# FPGA_C.net
KiCad netlist of a schematic drawn in Altium Designer
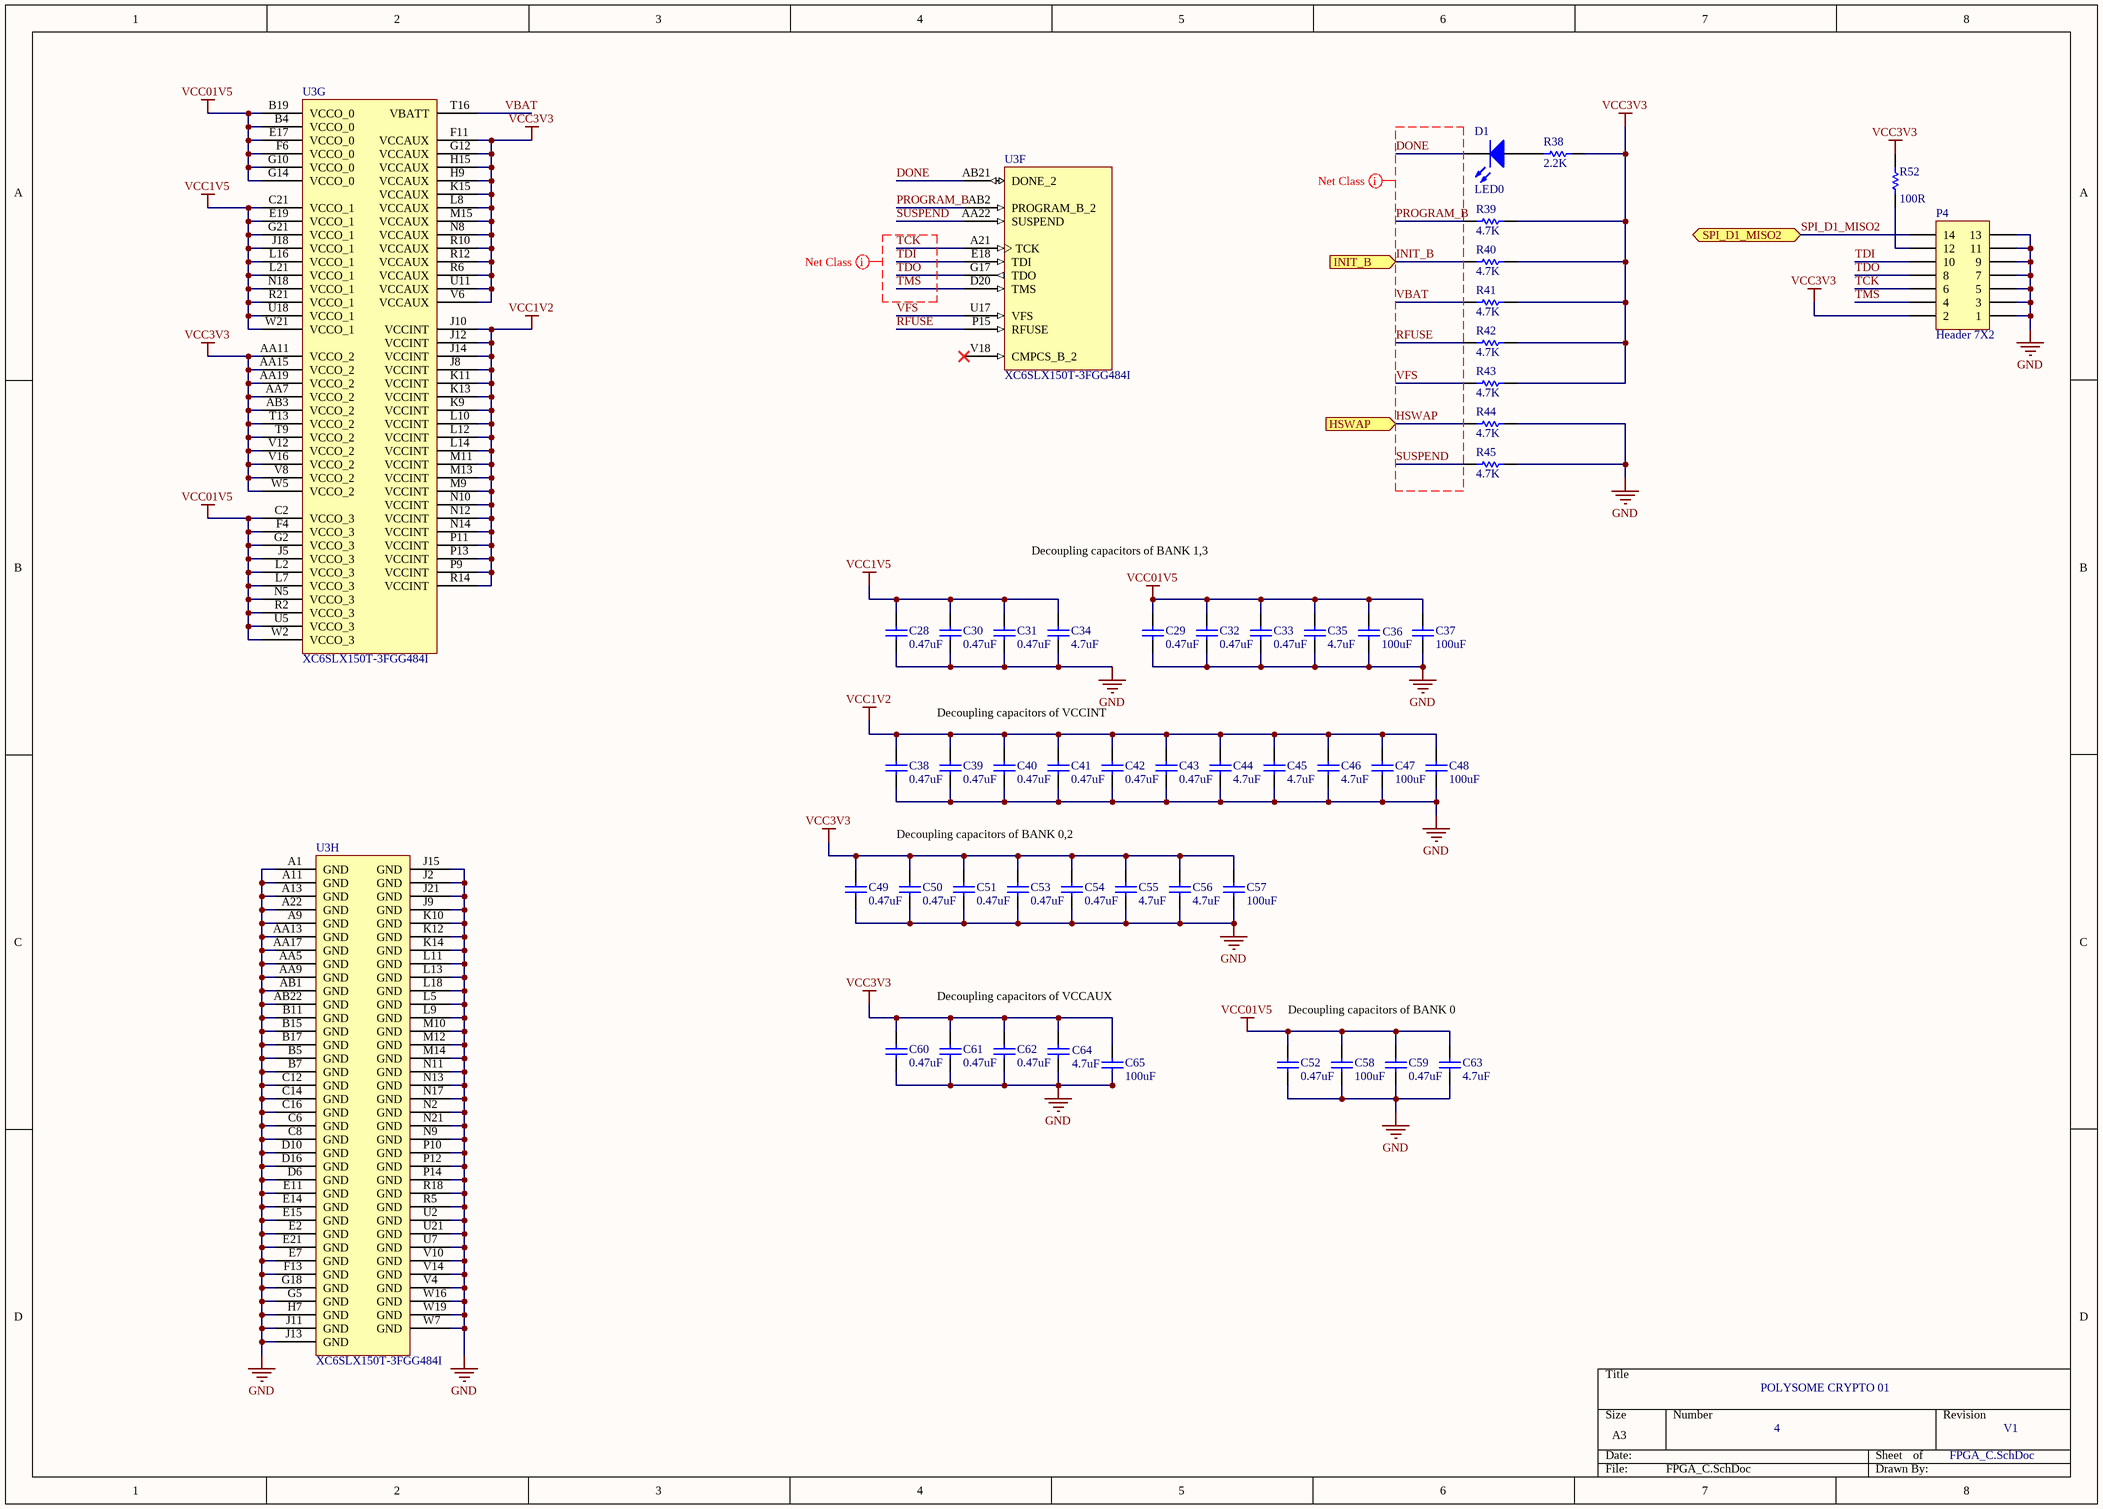
[diagram p0: FPGA_C.SchDoc]

(export (version "E")
  (design (tool "Eeschema 10.0.6"))
  (components
    (comp (ref "C28")
      (value "0.47uF")
      (footprint "0402")
      (description "Capacitor (Semiconductor SIM Model)")
      (fields (field (name "Comment") "Cap Semi") (field (name "PUBLISHER") "Altium Limited"))
      (libsource (lib "Miscellaneous Devices") (part "Cap Semi"))
    )
    (comp (ref "C29")
      (value "0.47uF")
      (footprint "0402")
      (description "Capacitor (Semiconductor SIM Model)")
      (fields (field (name "Comment") "Cap Semi") (field (name "PUBLISHER") "Altium Limited"))
      (libsource (lib "Miscellaneous Devices") (part "Cap Semi"))
    )
    (comp (ref "C30")
      (value "0.47uF")
      (footprint "0402")
      (description "Capacitor (Semiconductor SIM Model)")
      (fields (field (name "Comment") "Cap Semi") (field (name "PUBLISHER") "Altium Limited"))
      (libsource (lib "Miscellaneous Devices") (part "Cap Semi"))
    )
    (comp (ref "C31")
      (value "0.47uF")
      (footprint "0402")
      (description "Capacitor (Semiconductor SIM Model)")
      (fields (field (name "Comment") "Cap Semi") (field (name "PUBLISHER") "Altium Limited"))
      (libsource (lib "Miscellaneous Devices") (part "Cap Semi"))
    )
    (comp (ref "C32")
      (value "0.47uF")
      (footprint "0402")
      (description "Capacitor (Semiconductor SIM Model)")
      (fields (field (name "Comment") "Cap Semi") (field (name "PUBLISHER") "Altium Limited"))
      (libsource (lib "Miscellaneous Devices") (part "Cap Semi"))
    )
    (comp (ref "C33")
      (value "0.47uF")
      (footprint "0402")
      (description "Capacitor (Semiconductor SIM Model)")
      (fields (field (name "Comment") "Cap Semi") (field (name "PUBLISHER") "Altium Limited"))
      (libsource (lib "Miscellaneous Devices") (part "Cap Semi"))
    )
    (comp (ref "C34")
      (value "4.7uF")
      (footprint "1608[0603]")
      (description "Capacitor (Semiconductor SIM Model)")
      (fields (field (name "Comment") "Cap Semi") (field (name "PUBLISHER") "Altium Limited"))
      (libsource (lib "Miscellaneous Devices") (part "Cap Semi"))
    )
    (comp (ref "C35")
      (value "4.7uF")
      (footprint "1608[0603]")
      (description "Capacitor (Semiconductor SIM Model)")
      (fields (field (name "Comment") "Cap Semi") (field (name "PUBLISHER") "Altium Limited"))
      (libsource (lib "Miscellaneous Devices") (part "Cap Semi"))
    )
    (comp (ref "C36")
      (value "100uF")
      (footprint "0402")
      (description "Capacitor (Semiconductor SIM Model)")
      (fields (field (name "Comment") "Cap Semi") (field (name "PUBLISHER") "Altium Limited"))
      (libsource (lib "Miscellaneous Devices") (part "Cap Semi"))
    )
    (comp (ref "C37")
      (value "100uF")
      (footprint "0402")
      (description "Capacitor (Semiconductor SIM Model)")
      (fields (field (name "Comment") "Cap Semi") (field (name "PUBLISHER") "Altium Limited"))
      (libsource (lib "Miscellaneous Devices") (part "Cap Semi"))
    )
    (comp (ref "C38")
      (value "0.47uF")
      (footprint "0402")
      (description "Capacitor (Semiconductor SIM Model)")
      (fields (field (name "Comment") "Cap Semi") (field (name "PUBLISHER") "Altium Limited"))
      (libsource (lib "Miscellaneous Devices") (part "Cap Semi"))
    )
    (comp (ref "C39")
      (value "0.47uF")
      (footprint "0402")
      (description "Capacitor (Semiconductor SIM Model)")
      (fields (field (name "Comment") "Cap Semi") (field (name "PUBLISHER") "Altium Limited"))
      (libsource (lib "Miscellaneous Devices") (part "Cap Semi"))
    )
    (comp (ref "C40")
      (value "0.47uF")
      (footprint "0402")
      (description "Capacitor (Semiconductor SIM Model)")
      (fields (field (name "Comment") "Cap Semi") (field (name "PUBLISHER") "Altium Limited"))
      (libsource (lib "Miscellaneous Devices") (part "Cap Semi"))
    )
    (comp (ref "C41")
      (value "0.47uF")
      (footprint "0402")
      (description "Capacitor (Semiconductor SIM Model)")
      (fields (field (name "Comment") "Cap Semi") (field (name "PUBLISHER") "Altium Limited"))
      (libsource (lib "Miscellaneous Devices") (part "Cap Semi"))
    )
    (comp (ref "C42")
      (value "0.47uF")
      (footprint "0402")
      (description "Capacitor (Semiconductor SIM Model)")
      (fields (field (name "Comment") "Cap Semi") (field (name "PUBLISHER") "Altium Limited"))
      (libsource (lib "Miscellaneous Devices") (part "Cap Semi"))
    )
    (comp (ref "C43")
      (value "0.47uF")
      (footprint "0402")
      (description "Capacitor (Semiconductor SIM Model)")
      (fields (field (name "Comment") "Cap Semi") (field (name "PUBLISHER") "Altium Limited"))
      (libsource (lib "Miscellaneous Devices") (part "Cap Semi"))
    )
    (comp (ref "C44")
      (value "4.7uF")
      (footprint "1608[0603]")
      (description "Capacitor (Semiconductor SIM Model)")
      (fields (field (name "Comment") "Cap Semi") (field (name "PUBLISHER") "Altium Limited"))
      (libsource (lib "Miscellaneous Devices") (part "Cap Semi"))
    )
    (comp (ref "C45")
      (value "4.7uF")
      (footprint "1608[0603]")
      (description "Capacitor (Semiconductor SIM Model)")
      (fields (field (name "Comment") "Cap Semi") (field (name "PUBLISHER") "Altium Limited"))
      (libsource (lib "Miscellaneous Devices") (part "Cap Semi"))
    )
    (comp (ref "C46")
      (value "4.7uF")
      (footprint "1608[0603]")
      (description "Capacitor (Semiconductor SIM Model)")
      (fields (field (name "Comment") "Cap Semi") (field (name "PUBLISHER") "Altium Limited"))
      (libsource (lib "Miscellaneous Devices") (part "Cap Semi"))
    )
    (comp (ref "C47")
      (value "100uF")
      (footprint "0402")
      (description "Capacitor (Semiconductor SIM Model)")
      (fields (field (name "Comment") "Cap Semi") (field (name "PUBLISHER") "Altium Limited"))
      (libsource (lib "Miscellaneous Devices") (part "Cap Semi"))
    )
    (comp (ref "C48")
      (value "100uF")
      (footprint "0402")
      (description "Capacitor (Semiconductor SIM Model)")
      (fields (field (name "Comment") "Cap Semi") (field (name "PUBLISHER") "Altium Limited"))
      (libsource (lib "Miscellaneous Devices") (part "Cap Semi"))
    )
    (comp (ref "C49")
      (value "0.47uF")
      (footprint "0402")
      (description "Capacitor (Semiconductor SIM Model)")
      (fields (field (name "Comment") "Cap Semi") (field (name "PUBLISHER") "Altium Limited"))
      (libsource (lib "Miscellaneous Devices") (part "Cap Semi"))
    )
    (comp (ref "C50")
      (value "0.47uF")
      (footprint "0402")
      (description "Capacitor (Semiconductor SIM Model)")
      (fields (field (name "Comment") "Cap Semi") (field (name "PUBLISHER") "Altium Limited"))
      (libsource (lib "Miscellaneous Devices") (part "Cap Semi"))
    )
    (comp (ref "C51")
      (value "0.47uF")
      (footprint "0402")
      (description "Capacitor (Semiconductor SIM Model)")
      (fields (field (name "Comment") "Cap Semi") (field (name "PUBLISHER") "Altium Limited"))
      (libsource (lib "Miscellaneous Devices") (part "Cap Semi"))
    )
    (comp (ref "C52")
      (value "0.47uF")
      (footprint "0402")
      (description "Capacitor (Semiconductor SIM Model)")
      (fields (field (name "Comment") "Cap Semi") (field (name "PUBLISHER") "Altium Limited"))
      (libsource (lib "Miscellaneous Devices") (part "Cap Semi"))
    )
    (comp (ref "C53")
      (value "0.47uF")
      (footprint "0402")
      (description "Capacitor (Semiconductor SIM Model)")
      (fields (field (name "Comment") "Cap Semi") (field (name "PUBLISHER") "Altium Limited"))
      (libsource (lib "Miscellaneous Devices") (part "Cap Semi"))
    )
    (comp (ref "C54")
      (value "0.47uF")
      (footprint "0402")
      (description "Capacitor (Semiconductor SIM Model)")
      (fields (field (name "Comment") "Cap Semi") (field (name "PUBLISHER") "Altium Limited"))
      (libsource (lib "Miscellaneous Devices") (part "Cap Semi"))
    )
    (comp (ref "C55")
      (value "4.7uF")
      (footprint "1608[0603]")
      (description "Capacitor (Semiconductor SIM Model)")
      (fields (field (name "Comment") "Cap Semi") (field (name "PUBLISHER") "Altium Limited"))
      (libsource (lib "Miscellaneous Devices") (part "Cap Semi"))
    )
    (comp (ref "C56")
      (value "4.7uF")
      (footprint "1608[0603]")
      (description "Capacitor (Semiconductor SIM Model)")
      (fields (field (name "Comment") "Cap Semi") (field (name "PUBLISHER") "Altium Limited"))
      (libsource (lib "Miscellaneous Devices") (part "Cap Semi"))
    )
    (comp (ref "C57")
      (value "100uF")
      (footprint "0402")
      (description "Capacitor (Semiconductor SIM Model)")
      (fields (field (name "Comment") "Cap Semi") (field (name "PUBLISHER") "Altium Limited"))
      (libsource (lib "Miscellaneous Devices") (part "Cap Semi"))
    )
    (comp (ref "C58")
      (value "100uF")
      (footprint "0402")
      (description "Capacitor (Semiconductor SIM Model)")
      (fields (field (name "Comment") "Cap Semi") (field (name "PUBLISHER") "Altium Limited"))
      (libsource (lib "Miscellaneous Devices") (part "Cap Semi"))
    )
    (comp (ref "C59")
      (value "0.47uF")
      (footprint "0402")
      (description "Capacitor (Semiconductor SIM Model)")
      (fields (field (name "Comment") "Cap Semi") (field (name "PUBLISHER") "Altium Limited"))
      (libsource (lib "Miscellaneous Devices") (part "Cap Semi"))
    )
    (comp (ref "C60")
      (value "0.47uF")
      (footprint "0402")
      (description "Capacitor (Semiconductor SIM Model)")
      (fields (field (name "Comment") "Cap Semi") (field (name "PUBLISHER") "Altium Limited"))
      (libsource (lib "Miscellaneous Devices") (part "Cap Semi"))
    )
    (comp (ref "C61")
      (value "0.47uF")
      (footprint "0402")
      (description "Capacitor (Semiconductor SIM Model)")
      (fields (field (name "Comment") "Cap Semi") (field (name "PUBLISHER") "Altium Limited"))
      (libsource (lib "Miscellaneous Devices") (part "Cap Semi"))
    )
    (comp (ref "C62")
      (value "0.47uF")
      (footprint "0402")
      (description "Capacitor (Semiconductor SIM Model)")
      (fields (field (name "Comment") "Cap Semi") (field (name "PUBLISHER") "Altium Limited"))
      (libsource (lib "Miscellaneous Devices") (part "Cap Semi"))
    )
    (comp (ref "C63")
      (value "4.7uF")
      (footprint "1608[0603]")
      (description "Capacitor (Semiconductor SIM Model)")
      (fields (field (name "Comment") "Cap Semi") (field (name "PUBLISHER") "Altium Limited"))
      (libsource (lib "Miscellaneous Devices") (part "Cap Semi"))
    )
    (comp (ref "C64")
      (value "4.7uF")
      (footprint "1608[0603]")
      (description "Capacitor (Semiconductor SIM Model)")
      (fields (field (name "Comment") "Cap Semi") (field (name "PUBLISHER") "Altium Limited"))
      (libsource (lib "Miscellaneous Devices") (part "Cap Semi"))
    )
    (comp (ref "C65")
      (value "100uF")
      (footprint "C1206")
      (description "Capacitor (Semiconductor SIM Model)")
      (fields (field (name "Comment") "Cap Semi") (field (name "PUBLISHER") "Altium Limited"))
      (libsource (lib "Miscellaneous Devices") (part "Cap Semi"))
    )
    (comp (ref "D1")
      (value "LED0")
      (footprint "1608[0603]")
      (description "Typical INFRARED GaAs LED")
      (fields (field (name "PUBLISHER") "Altium Limited"))
      (libsource (lib "Miscellaneous Devices") (part "LED0"))
    )
    (comp (ref "P4")
      (value "Header 7X2")
      (footprint "JTAG_WM9059CT-ND")
      (description "Header, 7-Pin, Dual row")
      (fields (field (name "PUBLISHER") "Altium Limited"))
      (libsource (lib "Miscellaneous Connectors") (part "Header 7X2"))
    )
    (comp (ref "R38")
      (value "2.2K")
      (footprint "0402")
      (description "Semiconductor Resistor")
      (fields (field (name "Comment") "Res Semi") (field (name "PUBLISHER") "Altium Limited"))
      (libsource (lib "Miscellaneous Devices") (part "Res Semi"))
    )
    (comp (ref "R39")
      (value "4.7K")
      (footprint "0402")
      (description "Semiconductor Resistor")
      (fields (field (name "Comment") "Res Semi") (field (name "PUBLISHER") "Altium Limited"))
      (libsource (lib "Miscellaneous Devices") (part "Res Semi"))
    )
    (comp (ref "R40")
      (value "4.7K")
      (footprint "0402")
      (description "Semiconductor Resistor")
      (fields (field (name "Comment") "Res Semi") (field (name "PUBLISHER") "Altium Limited"))
      (libsource (lib "Miscellaneous Devices") (part "Res Semi"))
    )
    (comp (ref "R41")
      (value "4.7K")
      (footprint "0402")
      (description "Semiconductor Resistor")
      (fields (field (name "Comment") "Res Semi") (field (name "PUBLISHER") "Altium Limited"))
      (libsource (lib "Miscellaneous Devices") (part "Res Semi"))
    )
    (comp (ref "R42")
      (value "4.7K")
      (footprint "0402")
      (description "Semiconductor Resistor")
      (fields (field (name "Comment") "Res Semi") (field (name "PUBLISHER") "Altium Limited"))
      (libsource (lib "Miscellaneous Devices") (part "Res Semi"))
    )
    (comp (ref "R43")
      (value "4.7K")
      (footprint "0402")
      (description "Semiconductor Resistor")
      (fields (field (name "Comment") "Res Semi") (field (name "PUBLISHER") "Altium Limited"))
      (libsource (lib "Miscellaneous Devices") (part "Res Semi"))
    )
    (comp (ref "R44")
      (value "4.7K")
      (footprint "0402")
      (description "Semiconductor Resistor")
      (fields (field (name "Comment") "Res Semi") (field (name "PUBLISHER") "Altium Limited"))
      (libsource (lib "Miscellaneous Devices") (part "Res Semi"))
    )
    (comp (ref "R45")
      (value "4.7K")
      (footprint "0402")
      (description "Semiconductor Resistor")
      (fields (field (name "Comment") "Res Semi") (field (name "PUBLISHER") "Altium Limited"))
      (libsource (lib "Miscellaneous Devices") (part "Res Semi"))
    )
    (comp (ref "R52")
      (value "100R")
      (footprint "0402")
      (description "Semiconductor Resistor")
      (fields (field (name "Comment") "Res Semi") (field (name "PUBLISHER") "Altium Limited"))
      (libsource (lib "Miscellaneous Devices") (part "Res Semi"))
    )
    (comp (ref "U3")
      (value "XC6SLX150T-3FGG484I")
      (footprint "FGG484")
      (fields (field (name "PUBLISHER") "Altium Limited"))
      (libsource (lib "Xilinx Spartan-6") (part "XC6SLX150T-3FGG484I"))
    )
  )
  (nets
    (net (code "1") (name "/DONE") (class "Default")
      (node (ref "D1") (pin "2") (pinfunction "K_2") (pintype "passive"))
      (node (ref "U3") (pin "AB21") (pinfunction "DONE_2_AB21") (pintype "bidirectional"))
    )
    (net (code "2") (name "/HSWAP") (class "Default")
      (node (ref "R44") (pin "2") (pinfunction "2_2") (pintype "passive"))
    )
    (net (code "3") (name "/INIT_B") (class "Default")
      (node (ref "R40") (pin "2") (pinfunction "2_2") (pintype "passive"))
    )
    (net (code "4") (name "/PROGRAM_B") (class "Default")
      (node (ref "R39") (pin "2") (pinfunction "2_2") (pintype "passive"))
      (node (ref "U3") (pin "AB2") (pinfunction "PROGRAM_B_2_AB2") (pintype "input"))
    )
    (net (code "5") (name "/RFUSE") (class "Default")
      (node (ref "R42") (pin "2") (pinfunction "2_2") (pintype "passive"))
      (node (ref "U3") (pin "P15") (pinfunction "RFUSE_P15") (pintype "input"))
    )
    (net (code "6") (name "/SPI_D1_MISO2") (class "Default")
      (node (ref "P4") (pin "14") (pinfunction "14_14") (pintype "passive"))
    )
    (net (code "7") (name "/SUSPEND") (class "Default")
      (node (ref "R45") (pin "2") (pinfunction "2_2") (pintype "passive"))
      (node (ref "U3") (pin "AA22") (pinfunction "SUSPEND_AA22") (pintype "input"))
    )
    (net (code "8") (name "/TCK") (class "Default")
      (node (ref "P4") (pin "6") (pinfunction "6_6") (pintype "passive"))
      (node (ref "U3") (pin "A21") (pinfunction "TCK_A21") (pintype "input"))
    )
    (net (code "9") (name "/TDI") (class "Default")
      (node (ref "P4") (pin "10") (pinfunction "10_10") (pintype "passive"))
      (node (ref "U3") (pin "E18") (pinfunction "TDI_E18") (pintype "input"))
    )
    (net (code "10") (name "/TDO") (class "Default")
      (node (ref "P4") (pin "8") (pinfunction "8_8") (pintype "passive"))
      (node (ref "U3") (pin "G17") (pinfunction "TDO_G17") (pintype "output"))
    )
    (net (code "11") (name "/TMS") (class "Default")
      (node (ref "P4") (pin "4") (pinfunction "4_4") (pintype "passive"))
      (node (ref "U3") (pin "D20") (pinfunction "TMS_D20") (pintype "input"))
    )
    (net (code "12") (name "/VBAT") (class "Default")
      (node (ref "R41") (pin "2") (pinfunction "2_2") (pintype "passive"))
      (node (ref "U3") (pin "T16") (pinfunction "VBATT_T16") (pintype "power_in"))
    )
    (net (code "13") (name "/VFS") (class "Default")
      (node (ref "R43") (pin "2") (pinfunction "2_2") (pintype "passive"))
      (node (ref "U3") (pin "U17") (pinfunction "VFS_U17") (pintype "input"))
    )
    (net (code "14") (name "GND") (class "Default")
      (node (ref "C28") (pin "1") (pinfunction "1_1") (pintype "passive"))
      (node (ref "C29") (pin "1") (pinfunction "1_1") (pintype "passive"))
      (node (ref "C30") (pin "1") (pinfunction "1_1") (pintype "passive"))
      (node (ref "C31") (pin "1") (pinfunction "1_1") (pintype "passive"))
      (node (ref "C32") (pin "1") (pinfunction "1_1") (pintype "passive"))
      (node (ref "C33") (pin "1") (pinfunction "1_1") (pintype "passive"))
      (node (ref "C34") (pin "1") (pinfunction "1_1") (pintype "passive"))
      (node (ref "C35") (pin "1") (pinfunction "1_1") (pintype "passive"))
      (node (ref "C36") (pin "1") (pinfunction "1_1") (pintype "passive"))
      (node (ref "C37") (pin "1") (pinfunction "1_1") (pintype "passive"))
      (node (ref "C38") (pin "1") (pinfunction "1_1") (pintype "passive"))
      (node (ref "C39") (pin "1") (pinfunction "1_1") (pintype "passive"))
      (node (ref "C40") (pin "1") (pinfunction "1_1") (pintype "passive"))
      (node (ref "C41") (pin "1") (pinfunction "1_1") (pintype "passive"))
      (node (ref "C42") (pin "1") (pinfunction "1_1") (pintype "passive"))
      (node (ref "C43") (pin "1") (pinfunction "1_1") (pintype "passive"))
      (node (ref "C44") (pin "1") (pinfunction "1_1") (pintype "passive"))
      (node (ref "C45") (pin "1") (pinfunction "1_1") (pintype "passive"))
      (node (ref "C46") (pin "1") (pinfunction "1_1") (pintype "passive"))
      (node (ref "C47") (pin "1") (pinfunction "1_1") (pintype "passive"))
      (node (ref "C48") (pin "1") (pinfunction "1_1") (pintype "passive"))
      (node (ref "C49") (pin "1") (pinfunction "1_1") (pintype "passive"))
      (node (ref "C50") (pin "1") (pinfunction "1_1") (pintype "passive"))
      (node (ref "C51") (pin "1") (pinfunction "1_1") (pintype "passive"))
      (node (ref "C52") (pin "1") (pinfunction "1_1") (pintype "passive"))
      (node (ref "C53") (pin "1") (pinfunction "1_1") (pintype "passive"))
      (node (ref "C54") (pin "1") (pinfunction "1_1") (pintype "passive"))
      (node (ref "C55") (pin "1") (pinfunction "1_1") (pintype "passive"))
      (node (ref "C56") (pin "1") (pinfunction "1_1") (pintype "passive"))
      (node (ref "C57") (pin "1") (pinfunction "1_1") (pintype "passive"))
      (node (ref "C58") (pin "1") (pinfunction "1_1") (pintype "passive"))
      (node (ref "C59") (pin "1") (pinfunction "1_1") (pintype "passive"))
      (node (ref "C60") (pin "1") (pinfunction "1_1") (pintype "passive"))
      (node (ref "C61") (pin "1") (pinfunction "1_1") (pintype "passive"))
      (node (ref "C62") (pin "1") (pinfunction "1_1") (pintype "passive"))
      (node (ref "C63") (pin "1") (pinfunction "1_1") (pintype "passive"))
      (node (ref "C64") (pin "1") (pinfunction "1_1") (pintype "passive"))
      (node (ref "C65") (pin "1") (pinfunction "1_1") (pintype "passive"))
      (node (ref "P4") (pin "1") (pinfunction "1_1") (pintype "passive"))
      (node (ref "P4") (pin "11") (pinfunction "11_11") (pintype "passive"))
      (node (ref "P4") (pin "13") (pinfunction "13_13") (pintype "passive"))
      (node (ref "P4") (pin "3") (pinfunction "3_3") (pintype "passive"))
      (node (ref "P4") (pin "5") (pinfunction "5_5") (pintype "passive"))
      (node (ref "P4") (pin "7") (pinfunction "7_7") (pintype "passive"))
      (node (ref "P4") (pin "9") (pinfunction "9_9") (pintype "passive"))
      (node (ref "R44") (pin "1") (pinfunction "1_1") (pintype "passive"))
      (node (ref "R45") (pin "1") (pinfunction "1_1") (pintype "passive"))
      (node (ref "U3") (pin "A1") (pinfunction "GND_A1") (pintype "power_in"))
      (node (ref "U3") (pin "A11") (pinfunction "GND_A11") (pintype "power_in"))
      (node (ref "U3") (pin "A13") (pinfunction "GND_A13") (pintype "power_in"))
      (node (ref "U3") (pin "A22") (pinfunction "GND_A22") (pintype "power_in"))
      (node (ref "U3") (pin "A9") (pinfunction "GND_A9") (pintype "power_in"))
      (node (ref "U3") (pin "AA13") (pinfunction "GND_AA13") (pintype "power_in"))
      (node (ref "U3") (pin "AA17") (pinfunction "GND_AA17") (pintype "power_in"))
      (node (ref "U3") (pin "AA5") (pinfunction "GND_AA5") (pintype "power_in"))
      (node (ref "U3") (pin "AA9") (pinfunction "GND_AA9") (pintype "power_in"))
      (node (ref "U3") (pin "AB1") (pinfunction "GND_AB1") (pintype "power_in"))
      (node (ref "U3") (pin "AB22") (pinfunction "GND_AB22") (pintype "power_in"))
      (node (ref "U3") (pin "B11") (pinfunction "GND_B11") (pintype "power_in"))
      (node (ref "U3") (pin "B15") (pinfunction "GND_B15") (pintype "power_in"))
      (node (ref "U3") (pin "B17") (pinfunction "GND_B17") (pintype "power_in"))
      (node (ref "U3") (pin "B5") (pinfunction "GND_B5") (pintype "power_in"))
      (node (ref "U3") (pin "B7") (pinfunction "GND_B7") (pintype "power_in"))
      (node (ref "U3") (pin "C12") (pinfunction "GND_C12") (pintype "power_in"))
      (node (ref "U3") (pin "C14") (pinfunction "GND_C14") (pintype "power_in"))
      (node (ref "U3") (pin "C16") (pinfunction "GND_C16") (pintype "power_in"))
      (node (ref "U3") (pin "C6") (pinfunction "GND_C6") (pintype "power_in"))
      (node (ref "U3") (pin "C8") (pinfunction "GND_C8") (pintype "power_in"))
      (node (ref "U3") (pin "D10") (pinfunction "GND_D10") (pintype "power_in"))
      (node (ref "U3") (pin "D16") (pinfunction "GND_D16") (pintype "power_in"))
      (node (ref "U3") (pin "D6") (pinfunction "GND_D6") (pintype "power_in"))
      (node (ref "U3") (pin "E11") (pinfunction "GND_E11") (pintype "power_in"))
      (node (ref "U3") (pin "E14") (pinfunction "GND_E14") (pintype "power_in"))
      (node (ref "U3") (pin "E15") (pinfunction "GND_E15") (pintype "power_in"))
      (node (ref "U3") (pin "E2") (pinfunction "GND_E2") (pintype "power_in"))
      (node (ref "U3") (pin "E21") (pinfunction "GND_E21") (pintype "power_in"))
      (node (ref "U3") (pin "E7") (pinfunction "GND_E7") (pintype "power_in"))
      (node (ref "U3") (pin "F13") (pinfunction "GND_F13") (pintype "power_in"))
      (node (ref "U3") (pin "G18") (pinfunction "GND_G18") (pintype "power_in"))
      (node (ref "U3") (pin "G5") (pinfunction "GND_G5") (pintype "power_in"))
      (node (ref "U3") (pin "H7") (pinfunction "GND_H7") (pintype "power_in"))
      (node (ref "U3") (pin "J11") (pinfunction "GND_J11") (pintype "power_in"))
      (node (ref "U3") (pin "J13") (pinfunction "GND_J13") (pintype "power_in"))
      (node (ref "U3") (pin "J15") (pinfunction "GND_J15") (pintype "power_in"))
      (node (ref "U3") (pin "J2") (pinfunction "GND_J2") (pintype "power_in"))
      (node (ref "U3") (pin "J21") (pinfunction "GND_J21") (pintype "power_in"))
      (node (ref "U3") (pin "J9") (pinfunction "GND_J9") (pintype "power_in"))
      (node (ref "U3") (pin "K10") (pinfunction "GND_K10") (pintype "power_in"))
      (node (ref "U3") (pin "K12") (pinfunction "GND_K12") (pintype "power_in"))
      (node (ref "U3") (pin "K14") (pinfunction "GND_K14") (pintype "power_in"))
      (node (ref "U3") (pin "L11") (pinfunction "GND_L11") (pintype "power_in"))
      (node (ref "U3") (pin "L13") (pinfunction "GND_L13") (pintype "power_in"))
      (node (ref "U3") (pin "L18") (pinfunction "GND_L18") (pintype "power_in"))
      (node (ref "U3") (pin "L5") (pinfunction "GND_L5") (pintype "power_in"))
      (node (ref "U3") (pin "L9") (pinfunction "GND_L9") (pintype "power_in"))
      (node (ref "U3") (pin "M10") (pinfunction "GND_M10") (pintype "power_in"))
      (node (ref "U3") (pin "M12") (pinfunction "GND_M12") (pintype "power_in"))
      (node (ref "U3") (pin "M14") (pinfunction "GND_M14") (pintype "power_in"))
      (node (ref "U3") (pin "N11") (pinfunction "GND_N11") (pintype "power_in"))
      (node (ref "U3") (pin "N13") (pinfunction "GND_N13") (pintype "power_in"))
      (node (ref "U3") (pin "N17") (pinfunction "GND_N17") (pintype "power_in"))
      (node (ref "U3") (pin "N2") (pinfunction "GND_N2") (pintype "power_in"))
      (node (ref "U3") (pin "N21") (pinfunction "GND_N21") (pintype "power_in"))
      (node (ref "U3") (pin "N9") (pinfunction "GND_N9") (pintype "power_in"))
      (node (ref "U3") (pin "P10") (pinfunction "GND_P10") (pintype "power_in"))
      (node (ref "U3") (pin "P12") (pinfunction "GND_P12") (pintype "power_in"))
      (node (ref "U3") (pin "P14") (pinfunction "GND_P14") (pintype "power_in"))
      (node (ref "U3") (pin "R18") (pinfunction "GND_R18") (pintype "power_in"))
      (node (ref "U3") (pin "R5") (pinfunction "GND_R5") (pintype "power_in"))
      (node (ref "U3") (pin "U2") (pinfunction "GND_U2") (pintype "power_in"))
      (node (ref "U3") (pin "U21") (pinfunction "GND_U21") (pintype "power_in"))
      (node (ref "U3") (pin "U7") (pinfunction "GND_U7") (pintype "power_in"))
      (node (ref "U3") (pin "V10") (pinfunction "GND_V10") (pintype "power_in"))
      (node (ref "U3") (pin "V14") (pinfunction "GND_V14") (pintype "power_in"))
      (node (ref "U3") (pin "V4") (pinfunction "GND_V4") (pintype "power_in"))
      (node (ref "U3") (pin "W16") (pinfunction "GND_W16") (pintype "power_in"))
      (node (ref "U3") (pin "W19") (pinfunction "GND_W19") (pintype "power_in"))
      (node (ref "U3") (pin "W7") (pinfunction "GND_W7") (pintype "power_in"))
    )
    (net (code "15") (name "Net-(D1-A)") (class "Default")
      (node (ref "D1") (pin "1") (pinfunction "A_1") (pintype "passive"))
      (node (ref "R38") (pin "2") (pinfunction "2_2") (pintype "passive"))
    )
    (net (code "16") (name "Net-(P4-Pad12)") (class "Default")
      (node (ref "P4") (pin "12") (pinfunction "12_12") (pintype "passive"))
      (node (ref "R52") (pin "1") (pinfunction "1_1") (pintype "passive"))
    )
    (net (code "17") (name "VCC1V2") (class "Default")
      (node (ref "C38") (pin "2") (pinfunction "2_2") (pintype "passive"))
      (node (ref "C39") (pin "2") (pinfunction "2_2") (pintype "passive"))
      (node (ref "C40") (pin "2") (pinfunction "2_2") (pintype "passive"))
      (node (ref "C41") (pin "2") (pinfunction "2_2") (pintype "passive"))
      (node (ref "C42") (pin "2") (pinfunction "2_2") (pintype "passive"))
      (node (ref "C43") (pin "2") (pinfunction "2_2") (pintype "passive"))
      (node (ref "C44") (pin "2") (pinfunction "2_2") (pintype "passive"))
      (node (ref "C45") (pin "2") (pinfunction "2_2") (pintype "passive"))
      (node (ref "C46") (pin "2") (pinfunction "2_2") (pintype "passive"))
      (node (ref "C47") (pin "2") (pinfunction "2_2") (pintype "passive"))
      (node (ref "C48") (pin "2") (pinfunction "2_2") (pintype "passive"))
      (node (ref "U3") (pin "J10") (pinfunction "VCCINT_J10") (pintype "power_in"))
      (node (ref "U3") (pin "J12") (pinfunction "VCCINT_J12") (pintype "power_in"))
      (node (ref "U3") (pin "J14") (pinfunction "VCCINT_J14") (pintype "power_in"))
      (node (ref "U3") (pin "J8") (pinfunction "VCCINT_J8") (pintype "power_in"))
      (node (ref "U3") (pin "K11") (pinfunction "VCCINT_K11") (pintype "power_in"))
      (node (ref "U3") (pin "K13") (pinfunction "VCCINT_K13") (pintype "power_in"))
      (node (ref "U3") (pin "K9") (pinfunction "VCCINT_K9") (pintype "power_in"))
      (node (ref "U3") (pin "L10") (pinfunction "VCCINT_L10") (pintype "power_in"))
      (node (ref "U3") (pin "L12") (pinfunction "VCCINT_L12") (pintype "power_in"))
      (node (ref "U3") (pin "L14") (pinfunction "VCCINT_L14") (pintype "power_in"))
      (node (ref "U3") (pin "M11") (pinfunction "VCCINT_M11") (pintype "power_in"))
      (node (ref "U3") (pin "M13") (pinfunction "VCCINT_M13") (pintype "power_in"))
      (node (ref "U3") (pin "M9") (pinfunction "VCCINT_M9") (pintype "power_in"))
      (node (ref "U3") (pin "N10") (pinfunction "VCCINT_N10") (pintype "power_in"))
      (node (ref "U3") (pin "N12") (pinfunction "VCCINT_N12") (pintype "power_in"))
      (node (ref "U3") (pin "N14") (pinfunction "VCCINT_N14") (pintype "power_in"))
      (node (ref "U3") (pin "P11") (pinfunction "VCCINT_P11") (pintype "power_in"))
      (node (ref "U3") (pin "P13") (pinfunction "VCCINT_P13") (pintype "power_in"))
      (node (ref "U3") (pin "P9") (pinfunction "VCCINT_P9") (pintype "power_in"))
      (node (ref "U3") (pin "R14") (pinfunction "VCCINT_R14") (pintype "power_in"))
    )
    (net (code "18") (name "VCC01V5") (class "Default")
      (node (ref "C29") (pin "2") (pinfunction "2_2") (pintype "passive"))
      (node (ref "C32") (pin "2") (pinfunction "2_2") (pintype "passive"))
      (node (ref "C33") (pin "2") (pinfunction "2_2") (pintype "passive"))
      (node (ref "C35") (pin "2") (pinfunction "2_2") (pintype "passive"))
      (node (ref "C36") (pin "2") (pinfunction "2_2") (pintype "passive"))
      (node (ref "C37") (pin "2") (pinfunction "2_2") (pintype "passive"))
      (node (ref "C52") (pin "2") (pinfunction "2_2") (pintype "passive"))
      (node (ref "C58") (pin "2") (pinfunction "2_2") (pintype "passive"))
      (node (ref "C59") (pin "2") (pinfunction "2_2") (pintype "passive"))
      (node (ref "C63") (pin "2") (pinfunction "2_2") (pintype "passive"))
      (node (ref "U3") (pin "B19") (pinfunction "VCCO_0_B19") (pintype "power_in"))
      (node (ref "U3") (pin "B4") (pinfunction "VCCO_0_B4") (pintype "power_in"))
      (node (ref "U3") (pin "C2") (pinfunction "VCCO_3_C2") (pintype "power_in"))
      (node (ref "U3") (pin "E17") (pinfunction "VCCO_0_E17") (pintype "power_in"))
      (node (ref "U3") (pin "F4") (pinfunction "VCCO_3_F4") (pintype "power_in"))
      (node (ref "U3") (pin "F6") (pinfunction "VCCO_0_F6") (pintype "power_in"))
      (node (ref "U3") (pin "G10") (pinfunction "VCCO_0_G10") (pintype "power_in"))
      (node (ref "U3") (pin "G14") (pinfunction "VCCO_0_G14") (pintype "power_in"))
      (node (ref "U3") (pin "G2") (pinfunction "VCCO_3_G2") (pintype "power_in"))
      (node (ref "U3") (pin "J5") (pinfunction "VCCO_3_J5") (pintype "power_in"))
      (node (ref "U3") (pin "L2") (pinfunction "VCCO_3_L2") (pintype "power_in"))
      (node (ref "U3") (pin "L7") (pinfunction "VCCO_3_L7") (pintype "power_in"))
      (node (ref "U3") (pin "N5") (pinfunction "VCCO_3_N5") (pintype "power_in"))
      (node (ref "U3") (pin "R2") (pinfunction "VCCO_3_R2") (pintype "power_in"))
      (node (ref "U3") (pin "U5") (pinfunction "VCCO_3_U5") (pintype "power_in"))
      (node (ref "U3") (pin "W2") (pinfunction "VCCO_3_W2") (pintype "power_in"))
    )
    (net (code "19") (name "VCC1V5") (class "Default")
      (node (ref "C28") (pin "2") (pinfunction "2_2") (pintype "passive"))
      (node (ref "C30") (pin "2") (pinfunction "2_2") (pintype "passive"))
      (node (ref "C31") (pin "2") (pinfunction "2_2") (pintype "passive"))
      (node (ref "C34") (pin "2") (pinfunction "2_2") (pintype "passive"))
      (node (ref "U3") (pin "C21") (pinfunction "VCCO_1_C21") (pintype "power_in"))
      (node (ref "U3") (pin "E19") (pinfunction "VCCO_1_E19") (pintype "power_in"))
      (node (ref "U3") (pin "G21") (pinfunction "VCCO_1_G21") (pintype "power_in"))
      (node (ref "U3") (pin "J18") (pinfunction "VCCO_1_J18") (pintype "power_in"))
      (node (ref "U3") (pin "L16") (pinfunction "VCCO_1_L16") (pintype "power_in"))
      (node (ref "U3") (pin "L21") (pinfunction "VCCO_1_L21") (pintype "power_in"))
      (node (ref "U3") (pin "N18") (pinfunction "VCCO_1_N18") (pintype "power_in"))
      (node (ref "U3") (pin "R21") (pinfunction "VCCO_1_R21") (pintype "power_in"))
      (node (ref "U3") (pin "U18") (pinfunction "VCCO_1_U18") (pintype "power_in"))
      (node (ref "U3") (pin "W21") (pinfunction "VCCO_1_W21") (pintype "power_in"))
    )
    (net (code "20") (name "VCC3V3") (class "Default")
      (node (ref "C49") (pin "2") (pinfunction "2_2") (pintype "passive"))
      (node (ref "C50") (pin "2") (pinfunction "2_2") (pintype "passive"))
      (node (ref "C51") (pin "2") (pinfunction "2_2") (pintype "passive"))
      (node (ref "C53") (pin "2") (pinfunction "2_2") (pintype "passive"))
      (node (ref "C54") (pin "2") (pinfunction "2_2") (pintype "passive"))
      (node (ref "C55") (pin "2") (pinfunction "2_2") (pintype "passive"))
      (node (ref "C56") (pin "2") (pinfunction "2_2") (pintype "passive"))
      (node (ref "C57") (pin "2") (pinfunction "2_2") (pintype "passive"))
      (node (ref "C60") (pin "2") (pinfunction "2_2") (pintype "passive"))
      (node (ref "C61") (pin "2") (pinfunction "2_2") (pintype "passive"))
      (node (ref "C62") (pin "2") (pinfunction "2_2") (pintype "passive"))
      (node (ref "C64") (pin "2") (pinfunction "2_2") (pintype "passive"))
      (node (ref "C65") (pin "2") (pinfunction "2_2") (pintype "passive"))
      (node (ref "P4") (pin "2") (pinfunction "2_2") (pintype "passive"))
      (node (ref "R38") (pin "1") (pinfunction "1_1") (pintype "passive"))
      (node (ref "R39") (pin "1") (pinfunction "1_1") (pintype "passive"))
      (node (ref "R40") (pin "1") (pinfunction "1_1") (pintype "passive"))
      (node (ref "R41") (pin "1") (pinfunction "1_1") (pintype "passive"))
      (node (ref "R42") (pin "1") (pinfunction "1_1") (pintype "passive"))
      (node (ref "R43") (pin "1") (pinfunction "1_1") (pintype "passive"))
      (node (ref "R52") (pin "2") (pinfunction "2_2") (pintype "passive"))
      (node (ref "U3") (pin "AA11") (pinfunction "VCCO_2_AA11") (pintype "power_in"))
      (node (ref "U3") (pin "AA15") (pinfunction "VCCO_2_AA15") (pintype "power_in"))
      (node (ref "U3") (pin "AA19") (pinfunction "VCCO_2_AA19") (pintype "power_in"))
      (node (ref "U3") (pin "AA7") (pinfunction "VCCO_2_AA7") (pintype "power_in"))
      (node (ref "U3") (pin "AB3") (pinfunction "VCCO_2_AB3") (pintype "power_in"))
      (node (ref "U3") (pin "F11") (pinfunction "VCCAUX_F11") (pintype "power_in"))
      (node (ref "U3") (pin "G12") (pinfunction "VCCAUX_G12") (pintype "power_in"))
      (node (ref "U3") (pin "H15") (pinfunction "VCCAUX_H15") (pintype "power_in"))
      (node (ref "U3") (pin "H9") (pinfunction "VCCAUX_H9") (pintype "power_in"))
      (node (ref "U3") (pin "K15") (pinfunction "VCCAUX_K15") (pintype "power_in"))
      (node (ref "U3") (pin "L8") (pinfunction "VCCAUX_L8") (pintype "power_in"))
      (node (ref "U3") (pin "M15") (pinfunction "VCCAUX_M15") (pintype "power_in"))
      (node (ref "U3") (pin "N8") (pinfunction "VCCAUX_N8") (pintype "power_in"))
      (node (ref "U3") (pin "R10") (pinfunction "VCCAUX_R10") (pintype "power_in"))
      (node (ref "U3") (pin "R12") (pinfunction "VCCAUX_R12") (pintype "power_in"))
      (node (ref "U3") (pin "R6") (pinfunction "VCCAUX_R6") (pintype "power_in"))
      (node (ref "U3") (pin "T13") (pinfunction "VCCO_2_T13") (pintype "power_in"))
      (node (ref "U3") (pin "T9") (pinfunction "VCCO_2_T9") (pintype "power_in"))
      (node (ref "U3") (pin "U11") (pinfunction "VCCAUX_U11") (pintype "power_in"))
      (node (ref "U3") (pin "V12") (pinfunction "VCCO_2_V12") (pintype "power_in"))
      (node (ref "U3") (pin "V16") (pinfunction "VCCO_2_V16") (pintype "power_in"))
      (node (ref "U3") (pin "V6") (pinfunction "VCCAUX_V6") (pintype "power_in"))
      (node (ref "U3") (pin "V8") (pinfunction "VCCO_2_V8") (pintype "power_in"))
      (node (ref "U3") (pin "W5") (pinfunction "VCCO_2_W5") (pintype "power_in"))
    )
    (net (code "21") (name "unconnected-(U3F-CMPCS_B_2-PadV18)") (class "Default")
      (node (ref "U3") (pin "V18") (pinfunction "CMPCS_B_2_V18") (pintype "input+no_connect"))
    )
  )
)
